# PowerManagment.net
KiCad netlist of a schematic drawn in Altium Designer
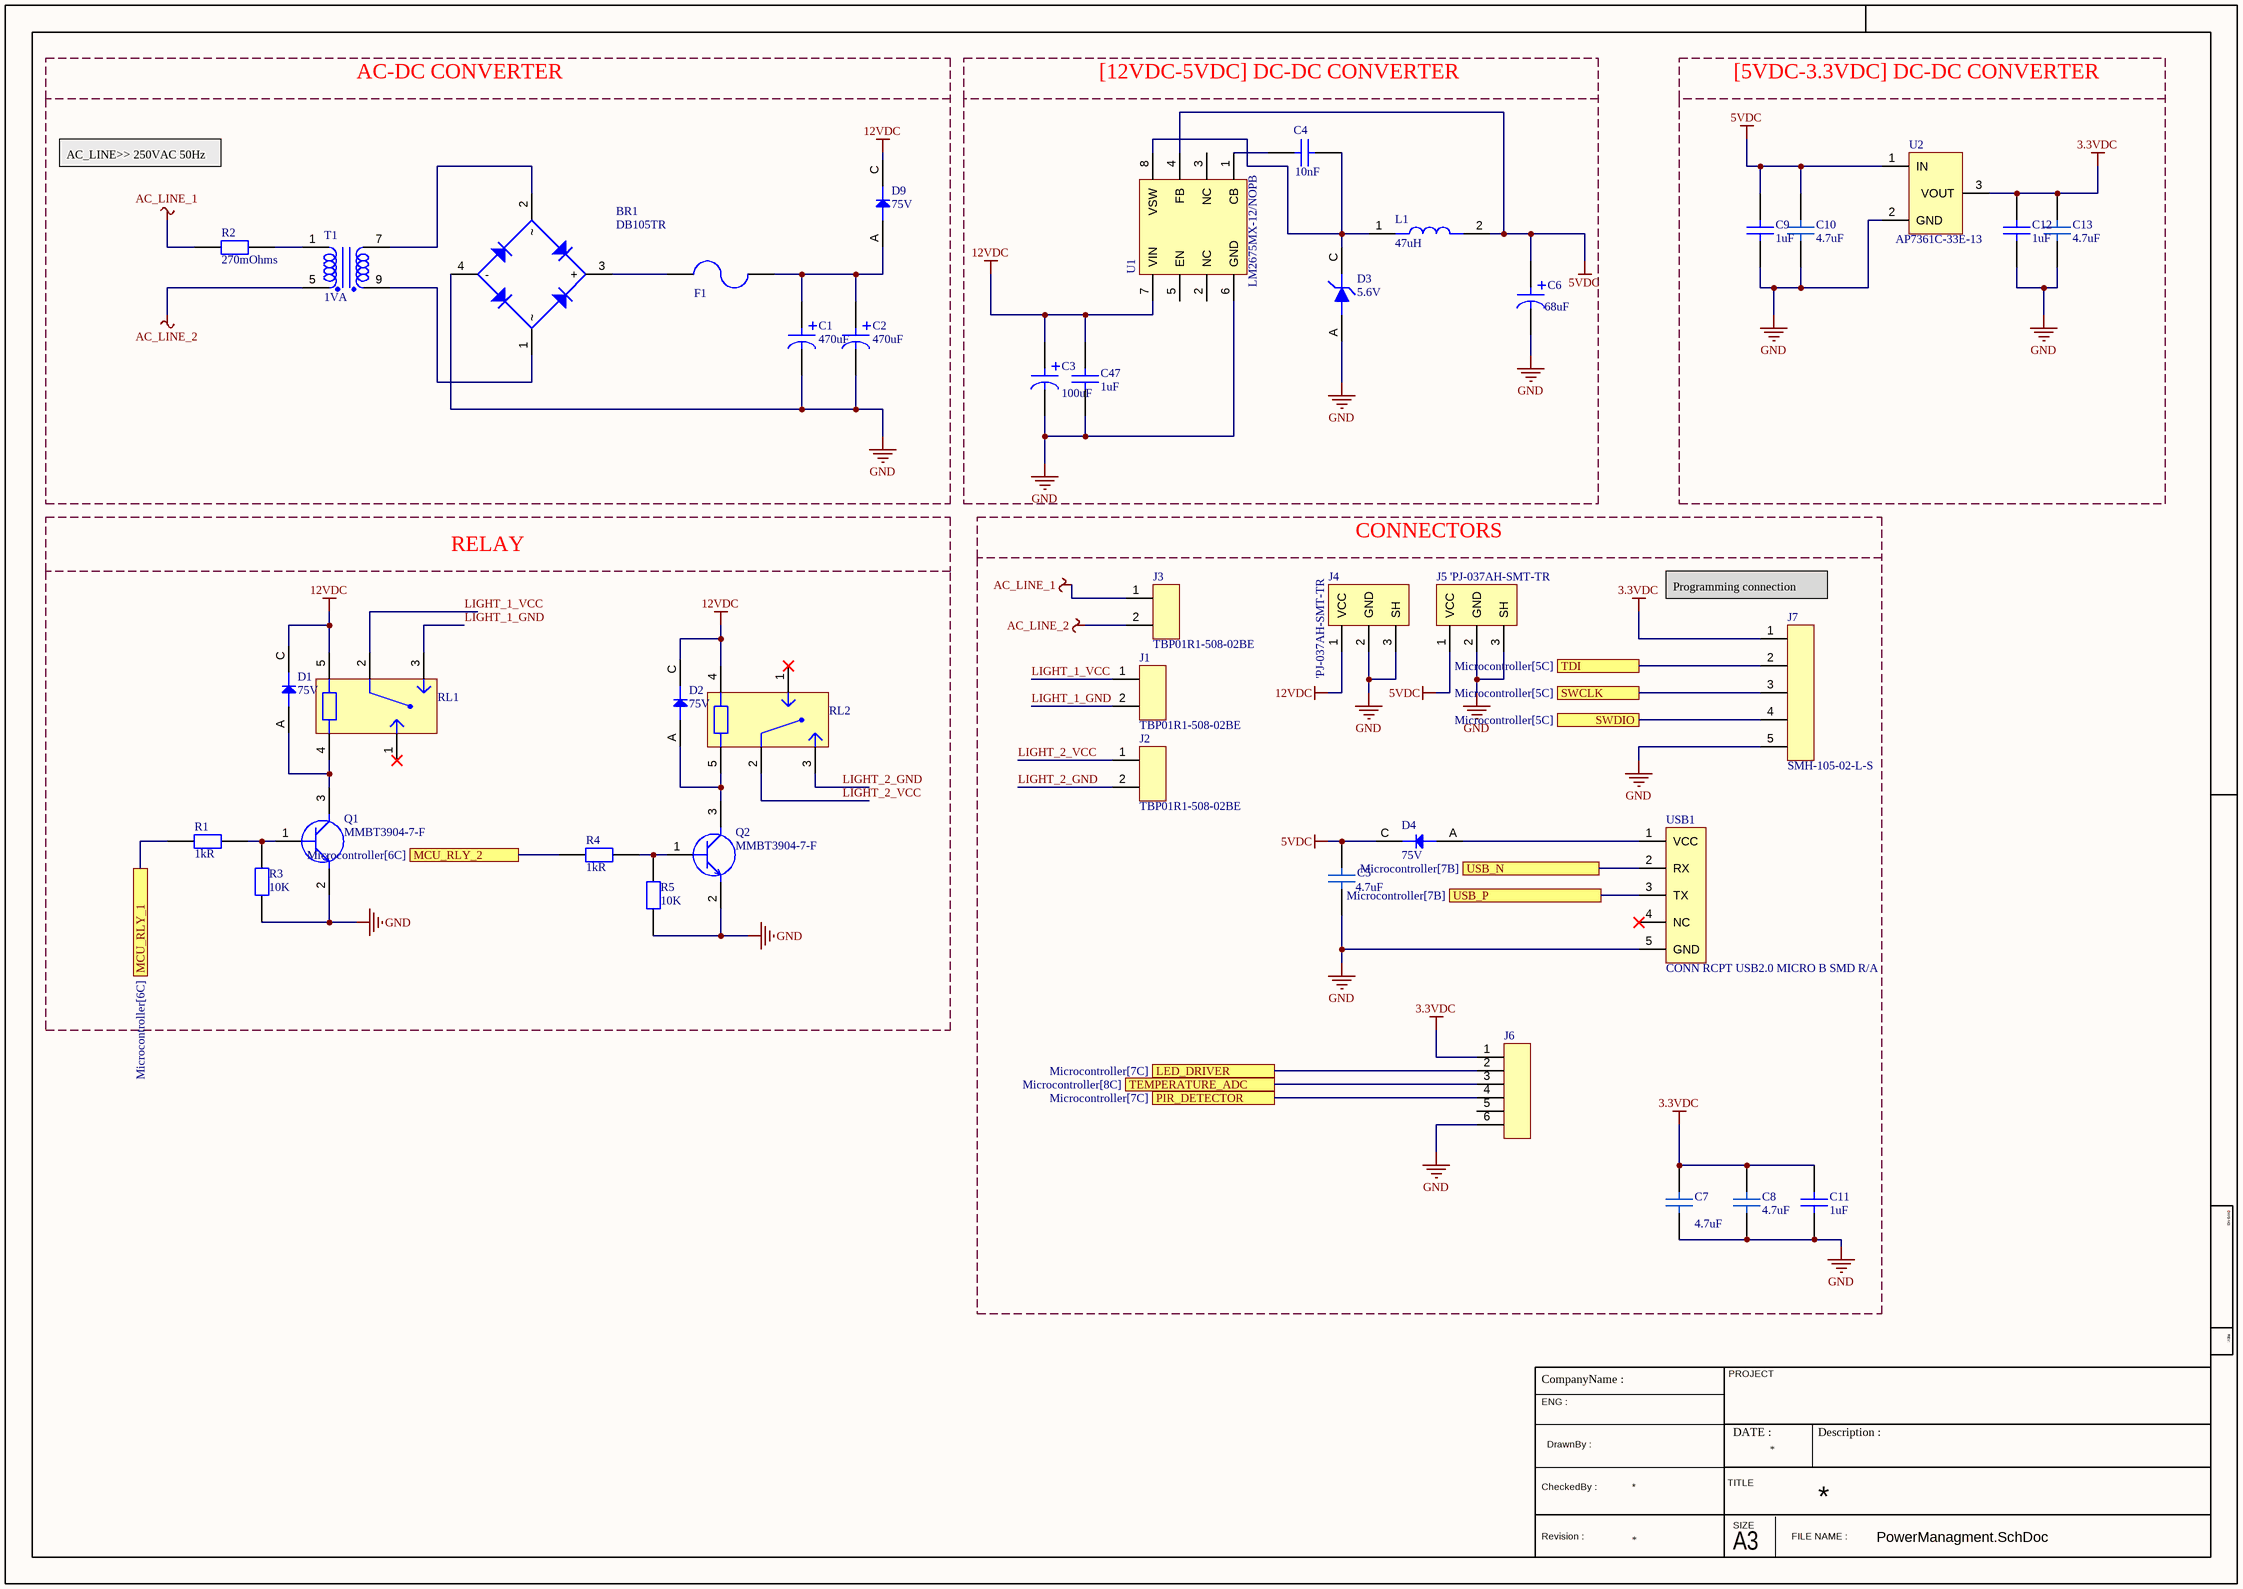
[diagram p0: PowerManagment.SchDoc]

(export (version "E")
  (design (tool "Eeschema 10.0.6"))
  (components
    (comp (ref "BR1")
      (value "DB105TR")
      (footprint "DB105S")
      (description "Bridge Rectifier, Full Wave, 600 Volt,")
      (fields
        (field (name "MANUFACTURER") "SMC Diode Solutions")
        (field (name "MANUFACTURER PART NUMBER") "DB105S")
        (field (name "DESIGNED BY") "Görkem Bulut")
      )
      (libsource (lib "ComplexCurcuit") (part "DB105TR"))
    )
    (comp (ref "C1")
      (value "ESH477M050AH4AA CAP")
      (footprint "CAP _RADİAL_D10_P5")
      (description "Cap, 470UF, 50V, Alu Elec, Radial")
      (fields
        (field (name "MANUFACTURER") "KEMET")
        (field (name "MANUFACTURER PART NUMBER") "ESH477M050AH4AA")
        (field (name "CAPACITANCE") "470uF")
        (field (name "DESIGNED BY") "Görkem Bulut")
      )
      (libsource (lib "ComplexCurcuit") (part "ESH477M050AH4AA CAP"))
    )
    (comp (ref "C2")
      (value "ESH477M050AH4AA CAP")
      (footprint "CAP _RADİAL_D10_P5")
      (description "Cap, 470UF, 50V, Alu Elec, Radial")
      (fields
        (field (name "MANUFACTURER") "KEMET")
        (field (name "MANUFACTURER PART NUMBER") "ESH477M050AH4AA")
        (field (name "CAPACITANCE") "470uF")
        (field (name "DESIGNED BY") "Görkem Bulut")
      )
      (libsource (lib "ComplexCurcuit") (part "ESH477M050AH4AA CAP"))
    )
    (comp (ref "C3")
      (value "UWT1H101MNL1GS")
      (footprint "CAP AEC Nichicon")
      (description "Aluminum Electrolytic Capacitor, 100uF 50 V dc, WT Series 1000h 8 (Dia.) x 10mm")
      (fields
        (field (name "MANUFACTURER") "Nichicon")
        (field (name "CAPACITY") "100uF")
        (field (name "DESIGNED BY") "Görkem BULUT")
      )
      (libsource (lib "ComplexCurcuit") (part "CAP CER 100uF AEC"))
    )
    (comp (ref "C4")
      (value "0603B103K160CT")
      (footprint "CAP 0603")
      (description "Multilayer Ceramic Capacitor, 0.01 F, 10%, X7R, 16 V, 0603 [1608 Metric] RoHS Compliant: Yes")
      (fields (field (name "MANUFACTURER") "Walsin Technologies") (field (name "CAPACITY") "10nF"))
      (libsource (lib "ComplexCurcuit") (part "CAP CER 10nF"))
    )
    (comp (ref "C5")
      (value "4.7uF")
      (footprint "CAP 0805")
      (description "CAP CER 4.7UF 25V X5R 0805")
      (fields
        (field (name "MANUFACTURER") "Samsung")
        (field (name "MANUFACTURER PART NUMBER") "CL21A475KAQNNNE")
      )
      (libsource (lib "ComplexCurcuit") (part "CAP CER 4.7uF"))
    )
    (comp (ref "C6")
      (value "EEV686M035A9HAA")
      (footprint "CAP_EEVSERİES")
      (description "Cap Aluminum Lytic 68uF 35V 20%( 6.3 X 7.7mm) SMD 0.34 Ohm 280mA 2000h 105C T/R")
      (fields
        (field (name "MANUFACTURER") "KEMET")
        (field (name "CAPACITANCE") "68uF")
        (field (name "DESIGNED BY") "Görkem Bulut")
      )
      (libsource (lib "ComplexCurcuit") (part "CAP 68uF AEC"))
    )
    (comp (ref "C7")
      (value "4.7uF")
      (footprint "CAP 0805")
      (description "CAP CER 4.7UF 25V X5R 0805")
      (fields
        (field (name "MANUFACTURER") "Samsung")
        (field (name "MANUFACTURER PART NUMBER") "CL21A475KAQNNNE")
      )
      (libsource (lib "ComplexCurcuit") (part "CAP CER 4.7uF"))
    )
    (comp (ref "C8")
      (value "4.7uF")
      (footprint "CAP 0805")
      (description "CAP CER 4.7UF 25V X5R 0805")
      (fields
        (field (name "MANUFACTURER") "Samsung")
        (field (name "MANUFACTURER PART NUMBER") "CL21A475KAQNNNE")
      )
      (libsource (lib "ComplexCurcuit") (part "CAP CER 4.7uF"))
    )
    (comp (ref "C9")
      (value "CAP CER 1UF 50V X7R 0805")
      (footprint "CAP 0805")
      (fields
        (field (name "MANUFACTURER") "Samsung")
        (field (name "MANUFACTURER PART NUMBER") "CL21B105KBFNNNE")
        (field (name "CAPACITANCE") "1uF")
        (field (name "DESIGNED BY") "Görkem Bulut")
      )
      (libsource (lib "ComplexCurcuit") (part "CAP CER 1uF"))
    )
    (comp (ref "C10")
      (value "4.7uF")
      (footprint "CAP 0805")
      (description "CAP CER 4.7UF 25V X5R 0805")
      (fields
        (field (name "MANUFACTURER") "Samsung")
        (field (name "MANUFACTURER PART NUMBER") "CL21A475KAQNNNE")
      )
      (libsource (lib "ComplexCurcuit") (part "CAP CER 4.7uF"))
    )
    (comp (ref "C11")
      (value "CAP CER 1UF 50V X7R 0805")
      (footprint "CAP 0805")
      (fields
        (field (name "MANUFACTURER") "Samsung")
        (field (name "MANUFACTURER PART NUMBER") "CL21B105KBFNNNE")
        (field (name "CAPACITANCE") "1uF")
        (field (name "DESIGNED BY") "Görkem Bulut")
      )
      (libsource (lib "ComplexCurcuit") (part "CAP CER 1uF"))
    )
    (comp (ref "C12")
      (value "CAP CER 1UF 50V X7R 0805")
      (footprint "CAP 0805")
      (fields
        (field (name "MANUFACTURER") "Samsung")
        (field (name "MANUFACTURER PART NUMBER") "CL21B105KBFNNNE")
        (field (name "CAPACITANCE") "1uF")
        (field (name "DESIGNED BY") "Görkem Bulut")
      )
      (libsource (lib "ComplexCurcuit") (part "CAP CER 1uF"))
    )
    (comp (ref "C13")
      (value "4.7uF")
      (footprint "CAP 0805")
      (description "CAP CER 4.7UF 25V X5R 0805")
      (fields
        (field (name "MANUFACTURER") "Samsung")
        (field (name "MANUFACTURER PART NUMBER") "CL21A475KAQNNNE")
      )
      (libsource (lib "ComplexCurcuit") (part "CAP CER 4.7uF"))
    )
    (comp (ref "C47")
      (value "CAP CER 1UF 50V X7R 0805")
      (footprint "CAP 0805")
      (fields
        (field (name "MANUFACTURER") "Samsung")
        (field (name "MANUFACTURER PART NUMBER") "CL21B105KBFNNNE")
        (field (name "CAPACITANCE") "1uF")
        (field (name "DESIGNED BY") "Görkem Bulut")
      )
      (libsource (lib "ComplexCurcuit") (part "CAP CER 1uF"))
    )
    (comp (ref "D1")
      (value "DIODE GEN PURP 75V 150MA SOD323F")
      (footprint "SOD323F")
      (description "VR=75V IF=150mA Trr=4ns P=200mW")
      (fields
        (field (name "MANUFACTURER") "ON Semiconductor / Fairchild")
        (field (name "MANUFACTURER PART NUMBER") "1N4148WS")
        (field (name "OPERATING VOLTAGE") "75V")
        (field (name "DESIGNED BY") "Görkem Bulut")
      )
      (libsource (lib "ComplexCurcuit") (part "1N4148WS"))
    )
    (comp (ref "D2")
      (value "DIODE GEN PURP 75V 150MA SOD323F")
      (footprint "SOD323F")
      (description "VR=75V IF=150mA Trr=4ns P=200mW")
      (fields
        (field (name "MANUFACTURER") "ON Semiconductor / Fairchild")
        (field (name "MANUFACTURER PART NUMBER") "1N4148WS")
        (field (name "OPERATING VOLTAGE") "75V")
        (field (name "DESIGNED BY") "Görkem Bulut")
      )
      (libsource (lib "ComplexCurcuit") (part "1N4148WS"))
    )
    (comp (ref "D3")
      (value "1SMB5919BT3G")
      (footprint "SMB")
      (description "Vz=5.6V 5.32V~5.88V Izt=66.9mA")
      (fields
        (field (name "MANUFACTURER") "ON Semiconductor")
        (field (name "WORKING VOLTAGE") "5.6V")
        (field (name "DESIGNED BY") "Görkem Bulut")
      )
      (libsource (lib "ComplexCurcuit") (part "1SMB5919BT3G"))
    )
    (comp (ref "D4")
      (value "DIODE GEN PURP 75V 150MA SOD323F")
      (footprint "SOD323F")
      (description "VR=75V IF=150mA Trr=4ns P=200mW")
      (fields
        (field (name "MANUFACTURER") "ON Semiconductor / Fairchild")
        (field (name "MANUFACTURER PART NUMBER") "1N4148WS")
        (field (name "OPERATING VOLTAGE") "75V")
        (field (name "DESIGNED BY") "Görkem Bulut")
      )
      (libsource (lib "ComplexCurcuit") (part "1N4148WS"))
    )
    (comp (ref "D9")
      (value "DIODE GEN PURP 75V 150MA SOD323F")
      (footprint "SOD323F")
      (description "VR=75V IF=150mA Trr=4ns P=200mW")
      (fields
        (field (name "MANUFACTURER") "ON Semiconductor / Fairchild")
        (field (name "MANUFACTURER PART NUMBER") "1N4148WS")
        (field (name "OPERATING VOLTAGE") "75V")
        (field (name "DESIGNED BY") "Görkem Bulut")
      )
      (libsource (lib "ComplexCurcuit") (part "1N4148WS"))
    )
    (comp (ref "F1")
      (value "3413.0216.22")
      (footprint "3413.0216.22 FUSE")
      (description "Fuse Chip Fast Acting 1A 32V SMD Solder Pad 1206 Glass T/R VDE/cULus")
      (fields (field (name "MANUFACTURER") "Schurter") (field (name "DESIGNED BY") "Görkem Bulut"))
      (libsource (lib "ComplexCurcuit") (part "FUSE 3413.0216.22"))
    )
    (comp (ref "J1")
      (value "TBP01R1-508-02BE")
      (footprint "TBP01R1-508")
      (description "2~24 Poles, Pluggable, Receptacle, Horizontal, 5.08 Pitch, Terminal Block Connector")
      (fields (field (name "MANUFACTURER") "CUI Devices") (field (name "DESIGNED BY") "GÖRKEM BULUT"))
      (libsource (lib "ComplexCurcuit") (part "TBP01R1-508-02BE"))
    )
    (comp (ref "J2")
      (value "TBP01R1-508-02BE")
      (footprint "TBP01R1-508")
      (description "2~24 Poles, Pluggable, Receptacle, Horizontal, 5.08 Pitch, Terminal Block Connector")
      (fields (field (name "MANUFACTURER") "CUI Devices") (field (name "DESIGNED BY") "GÖRKEM BULUT"))
      (libsource (lib "ComplexCurcuit") (part "TBP01R1-508-02BE"))
    )
    (comp (ref "J3")
      (value "TBP01R1-508-02BE")
      (footprint "TBP01R1-508")
      (description "2~24 Poles, Pluggable, Receptacle, Horizontal, 5.08 Pitch, Terminal Block Connector")
      (fields (field (name "MANUFACTURER") "CUI Devices") (field (name "DESIGNED BY") "GÖRKEM BULUT"))
      (libsource (lib "ComplexCurcuit") (part "TBP01R1-508-02BE"))
    )
    (comp (ref "J4")
      (value "'PJ-037AH-SMT-TR")
      (footprint "JACK")
      (description "2.0 x 6.3 mm, 5.0 A, Horizontal, Surface Mount (SMT), Dc Power Jack Connector")
      (fields
        (field (name "MANUFACTURER") "CUI")
        (field (name "MANUFACTURER PART NUMBER") "PJ-037AH-SMT-TR")
        (field (name "DESIGNED BY") "Görkem Bulut")
      )
      (libsource (lib "ComplexCurcuit") (part "PJ-037AH-SMT-TR"))
    )
    (comp (ref "J5")
      (value "'PJ-037AH-SMT-TR")
      (footprint "JACK")
      (description "2.0 x 6.3 mm, 5.0 A, Horizontal, Surface Mount (SMT), Dc Power Jack Connector")
      (fields
        (field (name "MANUFACTURER") "CUI")
        (field (name "MANUFACTURER PART NUMBER") "PJ-037AH-SMT-TR")
        (field (name "DESIGNED BY") "Görkem Bulut")
      )
      (libsource (lib "ComplexCurcuit") (part "PJ-037AH-SMT-TR"))
    )
    (comp (ref "J6")
      (value "64800611622 Datasheet WR-WTB Male Vertical Shrouded Header")
      (footprint "64800611622 Connector-1x6 Male Header")
      (description "WR-WTB Wire-to-Board Connectors 1.50 mm")
      (fields
        (field (name "MANUFACTURER") "Wurth Electronics")
        (field (name "MANUFACTURER PART NUMBER") "64800611622")
        (field (name "DESIGNED BY") "Görkem Bulut")
      )
      (libsource (lib "ComplexCurcuit") (part "1x6 Male Header-64800611622 Connector"))
    )
    (comp (ref "J7")
      (value "SMH-105-02-L-S")
      (footprint "SMH-105-02-L-S")
      (description ".100 C.L. HORIZONTAL SMT SOCKET")
      (fields (field (name "MANUFACTURER") "Samtec"))
      (libsource (lib "ComplexCurcuit") (part "SMH-105-02-L-S"))
    )
    (comp (ref "L1")
      (value "47uH")
      (footprint "IND_1212")
      (description "Power Inductor, Aec-Q200, 47Uh, 0.39A Rohs Compliant: Yes ¦Wurth Elektronik 78438335470")
      (fields
        (field (name "MANUFACTURER") "Wurth Electronics")
        (field (name "MANUFACTURER PART NUMBER") "78438335470")
        (field (name "DESIGNED BY") "Görkem Bulut")
      )
      (libsource (lib "ComplexCurcuit") (part "IND 47uH"))
    )
    (comp (ref "Q1")
      (value "MMBT3904-7-F")
      (footprint "SOT23F")
      (description "Transistor General Purpose BJT NPN 40 Volt 0.2A Automotive 3-Pin SOT-23")
      (fields (field (name "MANUFACTURER") "Diodes Zetex") (field (name "DESIGNED BY") "Gökem Bulut"))
      (libsource (lib "ComplexCurcuit") (part "MMBT3904-7-F"))
    )
    (comp (ref "Q2")
      (value "MMBT3904-7-F")
      (footprint "SOT23F")
      (description "Transistor General Purpose BJT NPN 40 Volt 0.2A Automotive 3-Pin SOT-23")
      (fields (field (name "MANUFACTURER") "Diodes Zetex") (field (name "DESIGNED BY") "Gökem Bulut"))
      (libsource (lib "ComplexCurcuit") (part "MMBT3904-7-F"))
    )
    (comp (ref "R1")
      (value "1kR")
      (footprint "RES 0603")
      (description "SMD Chip Resistor, 1 kOhm, ± 1%, 100 mW, 0603 [1608 Metric], Thick Film, General Purpose")
      (fields
        (field (name "MANUFACTURER") "Yageo")
        (field (name "MANUFACTURER PART NUMBER") "RC0603FR-071KL")
        (field (name "DESIGNED BY") "Görkem B.")
      )
      (libsource (lib "ComplexCurcuit") (part "RES 1K OHM"))
    )
    (comp (ref "R2")
      (value "5WD27")
      (footprint "RES_AXİAL_W")
      (description "270 mOhms ±5% 5W Through Hole Resistor Axial Wirewound")
      (fields
        (field (name "MANUFACTURER") "NTE Electronics, Inc")
        (field (name "TOLERANCE") "%5")
        (field (name "RESISTANCE") "270mOhms")
        (field (name "DESIGNED BY") "Görkem Bulut")
      )
      (libsource (lib "ComplexCurcuit") (part "5WD27"))
    )
    (comp (ref "R3")
      (value "RES 10K OHM  06103")
      (footprint "RES 0603")
      (description "RES SMD 10K OHM 1% 1/10W 0603")
      (fields
        (field (name "MANUFACTURER") "Yageo")
        (field (name "MANUFACTURER PART NUMBER") "RC0603FR-0710KL")
        (field (name "RESISTANCE") "10K")
        (field (name "DESIGNED BY") "Görkem Bulut")
      )
      (libsource (lib "ComplexCurcuit") (part "RES 10K OHM  06103"))
    )
    (comp (ref "R4")
      (value "1kR")
      (footprint "RES 0603")
      (description "SMD Chip Resistor, 1 kOhm, ± 1%, 100 mW, 0603 [1608 Metric], Thick Film, General Purpose")
      (fields
        (field (name "MANUFACTURER") "Yageo")
        (field (name "MANUFACTURER PART NUMBER") "RC0603FR-071KL")
        (field (name "DESIGNED BY") "Görkem B.")
      )
      (libsource (lib "ComplexCurcuit") (part "RES 1K OHM"))
    )
    (comp (ref "R5")
      (value "RES 10K OHM  06103")
      (footprint "RES 0603")
      (description "RES SMD 10K OHM 1% 1/10W 0603")
      (fields
        (field (name "MANUFACTURER") "Yageo")
        (field (name "MANUFACTURER PART NUMBER") "RC0603FR-0710KL")
        (field (name "RESISTANCE") "10K")
        (field (name "DESIGNED BY") "Görkem Bulut")
      )
      (libsource (lib "ComplexCurcuit") (part "RES 10K OHM  06103"))
    )
    (comp (ref "RL1")
      (value "ALQ112")
      (footprint "ALQ112")
      (description "RELAY GEN PURPOSE SPDT 10A 12V")
      (fields (field (name "MANUFACTURER") "Panasonic") (field (name "DESIGNED BY") "Görkem Bulut"))
      (libsource (lib "ComplexCurcuit") (part "ALQ112"))
    )
    (comp (ref "RL2")
      (value "ALQ112")
      (footprint "ALQ112")
      (description "RELAY GEN PURPOSE SPDT 10A 12V")
      (fields (field (name "MANUFACTURER") "Panasonic") (field (name "DESIGNED BY") "Görkem Bulut"))
      (libsource (lib "") (part "ALQ112_1"))
    )
    (comp (ref "T1")
      (value "BV302S12010")
      (footprint "BV302S")
      (description "Sealed Transformer EI30/10.5")
      (fields
        (field (name "MANUFACTURER") "Zettler Magnetics")
        (field (name "RATED POWER") "1VA")
        (field (name "DESIGNED BY") "Görkem Bulut")
      )
      (libsource (lib "ComplexCurcuit") (part "BV302S12010"))
    )
    (comp (ref "U1")
      (value "LM2675MX-12/NOPB")
      (footprint "SOIC8")
      (description "Buck Switching Regulator IC Positive Fixed 12V 1 Output 1A 8-SOIC (0.154\", 3.90mm Width)")
      (fields
        (field (name "MANUFACTURER") "TI National Semiconductor")
        (field (name "DESIGNED BY") "Görkem Bulut")
      )
      (libsource (lib "ComplexCurcuit") (part "LM2675MX-12/NOPB"))
    )
    (comp (ref "U2")
      (value "AP7361C-33E-13")
      (footprint "SOT223")
      (description "LDO Regulator Pos 3.3V 1A 4-Pin(3+Tab) SOT-223 T/R")
      (fields (field (name "MANUFACTURER") "Diodes") (field (name "DESIGNED BY") "Görkem Bulut"))
      (libsource (lib "ComplexCurcuit") (part "AP7361C-33E-13"))
    )
    (comp (ref "USB1")
      (value "CONN RCPT USB2.0 MICRO B SMD R/A")
      (footprint "Micro B USB Connector")
      (description "CONN USB MICRO B RECPT SMT R/A")
      (fields
        (field (name "MANUFACTURER") "Amphenol ICC / FCI")
        (field (name "MANUFACTURER PART NUMBER") "10118192-0001LF")
        (field (name "DESIGNED BY") "Görkem BULUT")
      )
      (libsource (lib "ComplexCurcuit") (part "Micro B USB Connector"))
    )
  )
  (nets
    (net (code "1") (name "/LED_DRIVER") (class "Default")
      (node (ref "J6") (pin "2") (pinfunction "2_2") (pintype "passive"))
    )
    (net (code "2") (name "/LIGHT_1_GND") (class "Default")
      (node (ref "J1") (pin "2") (pinfunction "2_2") (pintype "power_in"))
      (node (ref "RL1") (pin "3") (pinfunction "3_3") (pintype "passive"))
    )
    (net (code "3") (name "/LIGHT_1_VCC") (class "Default")
      (node (ref "J1") (pin "1") (pinfunction "1_1") (pintype "power_in"))
      (node (ref "RL1") (pin "2") (pinfunction "2_2") (pintype "passive"))
    )
    (net (code "4") (name "/LIGHT_2_GND") (class "Default")
      (node (ref "J2") (pin "2") (pinfunction "2_2") (pintype "power_in"))
      (node (ref "RL2") (pin "3") (pinfunction "3_3") (pintype "passive"))
    )
    (net (code "5") (name "/LIGHT_2_VCC") (class "Default")
      (node (ref "J2") (pin "1") (pinfunction "1_1") (pintype "power_in"))
      (node (ref "RL2") (pin "2") (pinfunction "2_2") (pintype "passive"))
    )
    (net (code "6") (name "/MCU_RLY_1") (class "Default")
      (node (ref "R1") (pin "1") (pinfunction "1_1") (pintype "passive"))
    )
    (net (code "7") (name "/MCU_RLY_2") (class "Default")
      (node (ref "R4") (pin "1") (pinfunction "1_1") (pintype "passive"))
    )
    (net (code "8") (name "/PIR_DETECTOR") (class "Default")
      (node (ref "J6") (pin "4") (pinfunction "4_4") (pintype "passive"))
    )
    (net (code "9") (name "/SWCLK") (class "Default")
      (node (ref "J7") (pin "3") (pinfunction "3_3") (pintype "power_in"))
    )
    (net (code "10") (name "/SWDIO") (class "Default")
      (node (ref "J7") (pin "4") (pinfunction "4_4") (pintype "power_in"))
    )
    (net (code "11") (name "/TDI") (class "Default")
      (node (ref "J7") (pin "2") (pinfunction "2_2") (pintype "power_in"))
    )
    (net (code "12") (name "/TEMPERATURE_ADC") (class "Default")
      (node (ref "J6") (pin "3") (pinfunction "3_3") (pintype "passive"))
    )
    (net (code "13") (name "/USB_N") (class "Default")
      (node (ref "USB1") (pin "2") (pinfunction "RX_2") (pintype "power_in"))
    )
    (net (code "14") (name "/USB_P") (class "Default")
      (node (ref "USB1") (pin "3") (pinfunction "TX_3") (pintype "power_in"))
    )
    (net (code "15") (name "3.3VDC") (class "Default")
      (node (ref "C11") (pin "2") (pinfunction "2_2") (pintype "passive"))
      (node (ref "C12") (pin "1") (pinfunction "1_1") (pintype "passive"))
      (node (ref "C13") (pin "1") (pinfunction "1_1") (pintype "passive"))
      (node (ref "C7") (pin "2") (pinfunction "2_2") (pintype "passive"))
      (node (ref "C8") (pin "2") (pinfunction "2_2") (pintype "passive"))
      (node (ref "J6") (pin "1") (pinfunction "1_1") (pintype "passive"))
      (node (ref "J7") (pin "1") (pinfunction "1_1") (pintype "power_in"))
      (node (ref "U2") (pin "3") (pinfunction "VOUT_3") (pintype "passive"))
    )
    (net (code "16") (name "5VDC") (class "Default")
      (node (ref "C10") (pin "1") (pinfunction "1_1") (pintype "passive"))
      (node (ref "C5") (pin "2") (pinfunction "2_2") (pintype "passive"))
      (node (ref "C6") (pin "1") (pinfunction "1_1") (pintype "passive"))
      (node (ref "C9") (pin "1") (pinfunction "1_1") (pintype "passive"))
      (node (ref "D4") (pin "C") (pinfunction "Cathode_C") (pintype "passive"))
      (node (ref "J5") (pin "1") (pinfunction "VCC_1") (pintype "power_in"))
      (node (ref "L1") (pin "2") (pinfunction "2_2") (pintype "passive"))
      (node (ref "U1") (pin "4") (pinfunction "FB_4") (pintype "passive"))
      (node (ref "U2") (pin "1") (pinfunction "IN_1") (pintype "passive"))
    )
    (net (code "17") (name "12VDC") (class "Default")
      (node (ref "C3") (pin "1") (pinfunction "1_1") (pintype "passive"))
      (node (ref "C47") (pin "1") (pinfunction "1_1") (pintype "passive"))
      (node (ref "D1") (pin "C") (pinfunction "Cathode_C") (pintype "passive"))
      (node (ref "D2") (pin "C") (pinfunction "Cathode_C") (pintype "passive"))
      (node (ref "D9") (pin "C") (pinfunction "Cathode_C") (pintype "passive"))
      (node (ref "J4") (pin "1") (pinfunction "VCC_1") (pintype "power_in"))
      (node (ref "RL1") (pin "5") (pinfunction "5_5") (pintype "passive"))
      (node (ref "RL2") (pin "4") (pinfunction "4_4") (pintype "passive"))
      (node (ref "U1") (pin "7") (pinfunction "VIN_7") (pintype "passive"))
    )
    (net (code "18") (name "AC_LINE_1") (class "Default")
      (node (ref "J3") (pin "1") (pinfunction "1_1") (pintype "power_in"))
      (node (ref "R2") (pin "1") (pinfunction "1_1") (pintype "passive"))
    )
    (net (code "19") (name "AC_LINE_2") (class "Default")
      (node (ref "J3") (pin "2") (pinfunction "2_2") (pintype "power_in"))
      (node (ref "T1") (pin "5") (pinfunction "5_5") (pintype "passive"))
    )
    (net (code "20") (name "GND") (class "Default")
      (node (ref "BR1") (pin "4") (pinfunction "-_4") (pintype "passive"))
      (node (ref "C1") (pin "2") (pinfunction "2_2") (pintype "passive"))
      (node (ref "C10") (pin "2") (pinfunction "2_2") (pintype "passive"))
      (node (ref "C11") (pin "1") (pinfunction "1_1") (pintype "passive"))
      (node (ref "C12") (pin "2") (pinfunction "2_2") (pintype "passive"))
      (node (ref "C13") (pin "2") (pinfunction "2_2") (pintype "passive"))
      (node (ref "C2") (pin "2") (pinfunction "2_2") (pintype "passive"))
      (node (ref "C3") (pin "2") (pinfunction "2_2") (pintype "passive"))
      (node (ref "C47") (pin "2") (pinfunction "2_2") (pintype "passive"))
      (node (ref "C5") (pin "1") (pinfunction "1_1") (pintype "passive"))
      (node (ref "C6") (pin "2") (pinfunction "2_2") (pintype "passive"))
      (node (ref "C7") (pin "1") (pinfunction "1_1") (pintype "passive"))
      (node (ref "C8") (pin "1") (pinfunction "1_1") (pintype "passive"))
      (node (ref "C9") (pin "2") (pinfunction "2_2") (pintype "passive"))
      (node (ref "D3") (pin "A") (pinfunction "Anode_A") (pintype "passive"))
      (node (ref "J4") (pin "2") (pinfunction "GND_2") (pintype "power_in"))
      (node (ref "J4") (pin "3") (pinfunction "SH_3") (pintype "passive"))
      (node (ref "J5") (pin "2") (pinfunction "GND_2") (pintype "power_in"))
      (node (ref "J5") (pin "3") (pinfunction "SH_3") (pintype "passive"))
      (node (ref "J6") (pin "6") (pinfunction "6_6") (pintype "passive"))
      (node (ref "J7") (pin "5") (pinfunction "5_5") (pintype "power_in"))
      (node (ref "Q1") (pin "2") (pinfunction "EMİTTER_2") (pintype "passive"))
      (node (ref "Q2") (pin "2") (pinfunction "EMİTTER_2") (pintype "passive"))
      (node (ref "R3") (pin "1") (pinfunction "1_1") (pintype "passive"))
      (node (ref "R5") (pin "1") (pinfunction "1_1") (pintype "passive"))
      (node (ref "U1") (pin "6") (pinfunction "GND_6") (pintype "passive"))
      (node (ref "U2") (pin "2") (pinfunction "GND_2") (pintype "passive"))
      (node (ref "USB1") (pin "5") (pinfunction "GND_5") (pintype "power_in"))
    )
    (net (code "21") (name "Net-(BR1-+)") (class "Default")
      (node (ref "BR1") (pin "3") (pinfunction "+_3") (pintype "passive"))
      (node (ref "F1") (pin "1") (pinfunction "1_1") (pintype "passive"))
    )
    (net (code "22") (name "Net-(BR1-~-Pad1)") (class "Default")
      (node (ref "BR1") (pin "1") (pinfunction "~_1") (pintype "passive"))
      (node (ref "T1") (pin "9") (pinfunction "9_9") (pintype "passive"))
    )
    (net (code "23") (name "Net-(BR1-~-Pad2)") (class "Default")
      (node (ref "BR1") (pin "2") (pinfunction "~_2") (pintype "passive"))
      (node (ref "T1") (pin "7") (pinfunction "7_7") (pintype "passive"))
    )
    (net (code "24") (name "Net-(D1-Anode)") (class "Default")
      (node (ref "D1") (pin "A") (pinfunction "Anode_A") (pintype "passive"))
      (node (ref "Q1") (pin "3") (pinfunction "CONNECTOR_3") (pintype "passive"))
      (node (ref "RL1") (pin "4") (pinfunction "4_4") (pintype "passive"))
    )
    (net (code "25") (name "Net-(D2-Anode)") (class "Default")
      (node (ref "D2") (pin "A") (pinfunction "Anode_A") (pintype "passive"))
      (node (ref "Q2") (pin "3") (pinfunction "CONNECTOR_3") (pintype "passive"))
      (node (ref "RL2") (pin "5") (pinfunction "5_5") (pintype "passive"))
    )
    (net (code "26") (name "Net-(D3-Cathode)") (class "Default")
      (node (ref "C4") (pin "2") (pinfunction "2_2") (pintype "passive"))
      (node (ref "D3") (pin "C") (pinfunction "Cathode_C") (pintype "passive"))
      (node (ref "L1") (pin "1") (pinfunction "1_1") (pintype "passive"))
      (node (ref "U1") (pin "8") (pinfunction "VSW_8") (pintype "passive"))
    )
    (net (code "27") (name "Net-(D4-Anode)") (class "Default")
      (node (ref "D4") (pin "A") (pinfunction "Anode_A") (pintype "passive"))
      (node (ref "USB1") (pin "1") (pinfunction "VCC_1") (pintype "power_in"))
    )
    (net (code "28") (name "Net-(D9-Anode)") (class "Default")
      (node (ref "C1") (pin "1") (pinfunction "1_1") (pintype "passive"))
      (node (ref "C2") (pin "1") (pinfunction "1_1") (pintype "passive"))
      (node (ref "D9") (pin "A") (pinfunction "Anode_A") (pintype "passive"))
      (node (ref "F1") (pin "2") (pinfunction "2_2") (pintype "passive"))
    )
    (net (code "29") (name "Net-(Q1-BASE)") (class "Default")
      (node (ref "Q1") (pin "1") (pinfunction "BASE_1") (pintype "passive"))
      (node (ref "R1") (pin "2") (pinfunction "2_2") (pintype "passive"))
      (node (ref "R3") (pin "2") (pinfunction "2_2") (pintype "passive"))
    )
    (net (code "30") (name "Net-(Q2-BASE)") (class "Default")
      (node (ref "Q2") (pin "1") (pinfunction "BASE_1") (pintype "passive"))
      (node (ref "R4") (pin "2") (pinfunction "2_2") (pintype "passive"))
      (node (ref "R5") (pin "2") (pinfunction "2_2") (pintype "passive"))
    )
    (net (code "31") (name "Net-(R2-Pad2)") (class "Default")
      (node (ref "R2") (pin "2") (pinfunction "2_2") (pintype "passive"))
      (node (ref "T1") (pin "1") (pinfunction "1_1") (pintype "passive"))
    )
    (net (code "32") (name "Net-(U1-CB)") (class "Default")
      (node (ref "C4") (pin "1") (pinfunction "1_1") (pintype "passive"))
      (node (ref "U1") (pin "1") (pinfunction "CB_1") (pintype "passive"))
    )
    (net (code "33") (name "unconnected-(J6-Pad5)") (class "Default")
      (node (ref "J6") (pin "5") (pinfunction "5_5") (pintype "passive"))
    )
    (net (code "34") (name "unconnected-(RL1-Pad1)") (class "Default")
      (node (ref "RL1") (pin "1") (pinfunction "1_1") (pintype "passive+no_connect"))
    )
    (net (code "35") (name "unconnected-(RL2-Pad1)") (class "Default")
      (node (ref "RL2") (pin "1") (pinfunction "1_1") (pintype "passive+no_connect"))
    )
    (net (code "36") (name "unconnected-(U1-EN-Pad5)") (class "Default")
      (node (ref "U1") (pin "5") (pinfunction "EN_5") (pintype "passive"))
    )
    (net (code "37") (name "unconnected-(U1-NC-Pad2)") (class "Default")
      (node (ref "U1") (pin "2") (pinfunction "NC_2") (pintype "passive"))
    )
    (net (code "38") (name "unconnected-(U1-NC-Pad3)") (class "Default")
      (node (ref "U1") (pin "3") (pinfunction "NC_3") (pintype "passive"))
    )
    (net (code "39") (name "unconnected-(USB1-NC-Pad4)") (class "Default")
      (node (ref "USB1") (pin "4") (pinfunction "NC_4") (pintype "power_in+no_connect"))
    )
  )
)
